# board.net
KiCad netlist of a schematic drawn in EAGLE
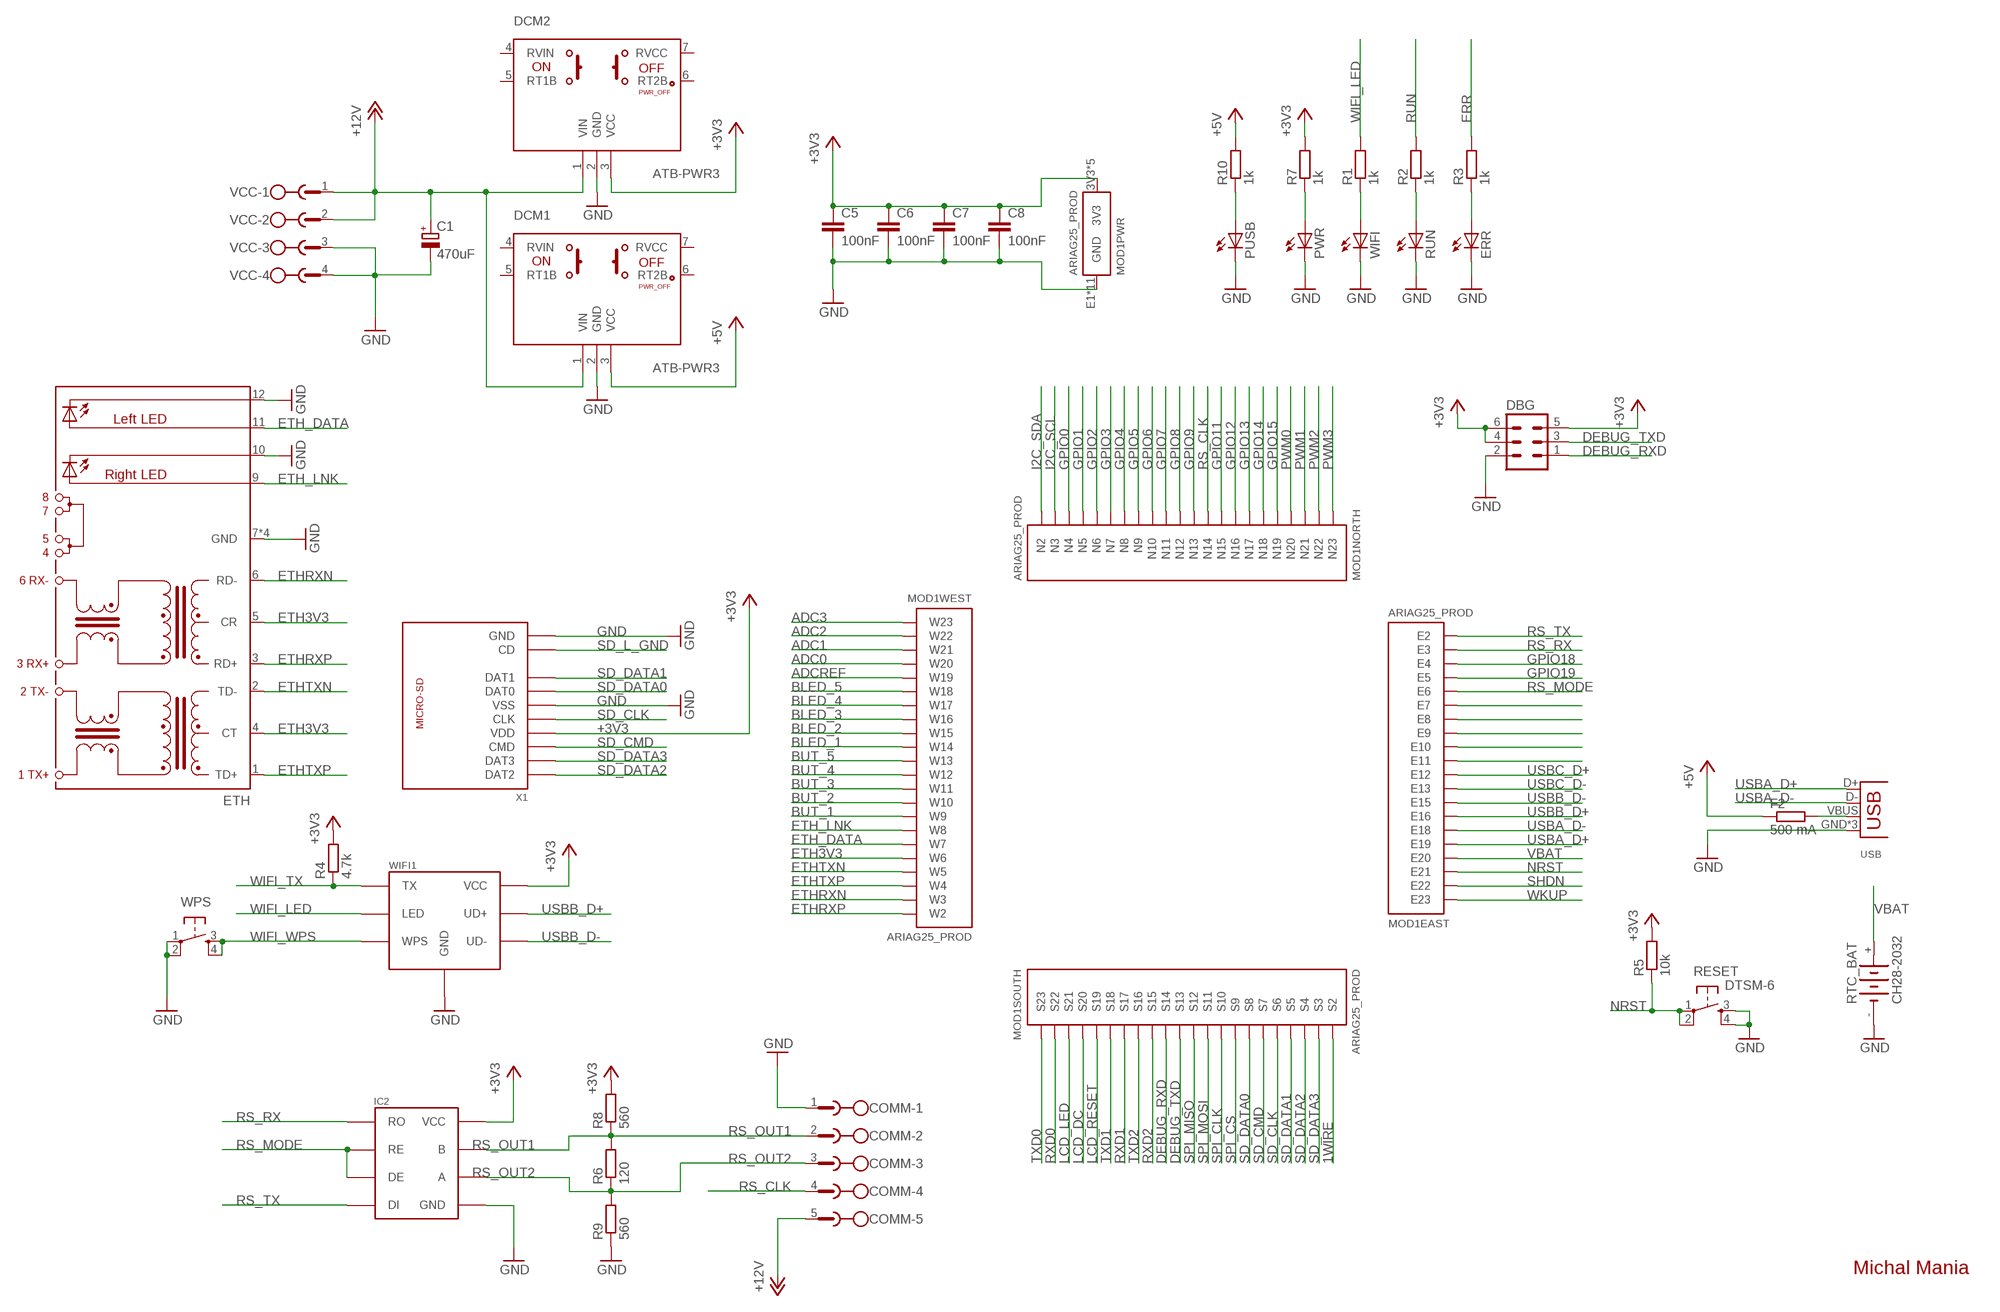
[diagram p0: schematic, sheet 1]

(export (version "E")
  (design (tool "Eeschema 10.0.6"))
  (components
    (comp (ref "C1")
      (value "470uF")
      (footprint "eagle-import:PANASONIC_G")
      (libsource (lib "eagle-import") (part "CPOL-EUG"))
    )
    (comp (ref "C5")
      (value "100nF")
      (footprint "eagle-import:C0805")
      (libsource (lib "eagle-import") (part "C-EUC0805"))
    )
    (comp (ref "C6")
      (value "100nF")
      (footprint "eagle-import:C0805")
      (libsource (lib "eagle-import") (part "C-EUC0805"))
    )
    (comp (ref "C7")
      (value "100nF")
      (footprint "eagle-import:C0805")
      (libsource (lib "eagle-import") (part "C-EUC0805"))
    )
    (comp (ref "C8")
      (value "100nF")
      (footprint "eagle-import:C0805")
      (libsource (lib "eagle-import") (part "C-EUC0805"))
    )
    (comp (ref "COMM")
      (value "MSTBV5")
      (footprint "eagle-import:MSTBV5")
      (fields (field (name "MPN") "MSTBV 2,5/5-GF-5.08"))
      (libsource (lib "eagle-import") (part "MSTBV5"))
    )
    (comp (ref "DBG")
      (value "MA03-2")
      (footprint "eagle-import:MA03-2")
      (fields (field (name "OC_FARNELL") "unknown") (field (name "OC_NEWARK") "unknown"))
      (libsource (lib "eagle-import") (part "MA03-2"))
    )
    (comp (ref "DCM1")
      (value "ATB-PWR3")
      (footprint "eagle-import:ATB-PWR3")
      (libsource (lib "eagle-import") (part "ATB-PWR3"))
    )
    (comp (ref "DCM2")
      (value "ATB-PWR3")
      (footprint "eagle-import:ATB-PWR3")
      (libsource (lib "eagle-import") (part "ATB-PWR3"))
    )
    (comp (ref "ERR")
      (value "LEDSML0805")
      (footprint "eagle-import:SML0805")
      (libsource (lib "eagle-import") (part "LEDSML0805"))
    )
    (comp (ref "ETH")
      (value "J21388")
      (footprint "eagle-import:J1_3_TOP")
      (libsource (lib "eagle-import") (part "J21388"))
    )
    (comp (ref "F2")
      (value "500 mA")
      (footprint "eagle-import:R0805")
      (libsource (lib "eagle-import") (part "R-EU_R0805"))
    )
    (comp (ref "IC2")
      (value "MAX3485")
      (footprint "eagle-import:SO-8")
      (libsource (lib "eagle-import") (part "MAX3485"))
    )
    (comp (ref "MOD1")
      (value "ARIAG25_PROD")
      (footprint "eagle-import:G25_D")
      (libsource (lib "eagle-import") (part "ARIAG25_PROD"))
    )
    (comp (ref "PUSB")
      (value "LEDSML0805")
      (footprint "eagle-import:SML0805")
      (libsource (lib "eagle-import") (part "LEDSML0805"))
    )
    (comp (ref "PWR")
      (value "LEDSML0805")
      (footprint "eagle-import:SML0805")
      (libsource (lib "eagle-import") (part "LEDSML0805"))
    )
    (comp (ref "R1")
      (value "1k")
      (footprint "eagle-import:R0805")
      (libsource (lib "eagle-import") (part "R-EU_R0805"))
    )
    (comp (ref "R2")
      (value "1k")
      (footprint "eagle-import:R0805")
      (libsource (lib "eagle-import") (part "R-EU_R0805"))
    )
    (comp (ref "R3")
      (value "1k")
      (footprint "eagle-import:R0805")
      (libsource (lib "eagle-import") (part "R-EU_R0805"))
    )
    (comp (ref "R4")
      (value "4.7k")
      (footprint "eagle-import:R0805")
      (libsource (lib "eagle-import") (part "R-EU_R0805"))
    )
    (comp (ref "R5")
      (value "10k")
      (footprint "eagle-import:R0805")
      (libsource (lib "eagle-import") (part "R-EU_R0805"))
    )
    (comp (ref "R6")
      (value "120")
      (footprint "eagle-import:R0805")
      (libsource (lib "eagle-import") (part "R-EU_R0805"))
    )
    (comp (ref "R7")
      (value "1k")
      (footprint "eagle-import:R0805")
      (libsource (lib "eagle-import") (part "R-EU_R0805"))
    )
    (comp (ref "R8")
      (value "560")
      (footprint "eagle-import:R0805")
      (libsource (lib "eagle-import") (part "R-EU_R0805"))
    )
    (comp (ref "R9")
      (value "560")
      (footprint "eagle-import:R0805")
      (libsource (lib "eagle-import") (part "R-EU_R0805"))
    )
    (comp (ref "R10")
      (value "1k")
      (footprint "eagle-import:R0805")
      (libsource (lib "eagle-import") (part "R-EU_R0805"))
    )
    (comp (ref "RESET")
      (value "DTSM-6")
      (footprint "eagle-import:DTSM-6")
      (libsource (lib "eagle-import") (part "DTSM-6"))
    )
    (comp (ref "RTC_BAT")
      (value "CH28-2032")
      (footprint "eagle-import:CH28-2032")
      (libsource (lib "eagle-import") (part "CH28-2032"))
    )
    (comp (ref "RUN")
      (value "LEDSML0805")
      (footprint "eagle-import:SML0805")
      (libsource (lib "eagle-import") (part "LEDSML0805"))
    )
    (comp (ref "USB")
      (value "USBA-P")
      (footprint "eagle-import:USB-A-P")
      (libsource (lib "eagle-import") (part "USBA-P"))
    )
    (comp (ref "VCC")
      (value "MSTBV4")
      (footprint "eagle-import:MSTBV4")
      (fields (field (name "MPN") "MSTBV 2,5/4-GF-5.08"))
      (libsource (lib "eagle-import") (part "MSTBV4"))
    )
    (comp (ref "WIFI")
      (value "LEDSML0805")
      (footprint "eagle-import:SML0805")
      (libsource (lib "eagle-import") (part "LEDSML0805"))
    )
    (comp (ref "WIFI1")
      (value "WIFI-2-OEM")
      (footprint "eagle-import:WIFI")
      (libsource (lib "eagle-import") (part "WIFI-2-OEM"))
    )
    (comp (ref "WPS")
      (value "DTSM-6")
      (footprint "eagle-import:DTSM-6")
      (libsource (lib "eagle-import") (part "DTSM-6"))
    )
    (comp (ref "X1")
      (value "MICRO-SD")
      (footprint "eagle-import:112I-TDAR-R")
      (libsource (lib "eagle-import") (part "MICRO-SD"))
    )
  )
  (nets
    (net (code "1") (name "+3V3") (class "Default")
      (node (ref "C5") (pin "1") (pinfunction "1_1") (pintype "passive"))
      (node (ref "C6") (pin "1") (pinfunction "1_1") (pintype "passive"))
      (node (ref "C7") (pin "1") (pinfunction "1_1") (pintype "passive"))
      (node (ref "C8") (pin "1") (pinfunction "1_1") (pintype "passive"))
      (node (ref "DBG") (pin "4") (pinfunction "4_4") (pintype "passive"))
      (node (ref "DBG") (pin "5") (pinfunction "5_5") (pintype "passive"))
      (node (ref "DBG") (pin "6") (pinfunction "6_6") (pintype "passive"))
      (node (ref "DCM2") (pin "3") (pinfunction "VCC_3") (pintype "power_in"))
      (node (ref "IC2") (pin "VCC") (pinfunction "VCC_VCC") (pintype "bidirectional"))
      (node (ref "MOD1") (pin "3V3") (pinfunction "3V3_3V3") (pintype "power_in"))
      (node (ref "MOD1") (pin "E24") (pinfunction "3V3_E24") (pintype "power_in"))
      (node (ref "MOD1") (pin "N1") (pinfunction "3V3_N1") (pintype "power_in"))
      (node (ref "MOD1") (pin "S1") (pinfunction "3V3_S1") (pintype "power_in"))
      (node (ref "MOD1") (pin "W24") (pinfunction "3V3_W24") (pintype "power_in"))
      (node (ref "R4") (pin "2") (pinfunction "2_2") (pintype "passive"))
      (node (ref "R5") (pin "2") (pinfunction "2_2") (pintype "passive"))
      (node (ref "R7") (pin "2") (pinfunction "2_2") (pintype "passive"))
      (node (ref "R8") (pin "2") (pinfunction "2_2") (pintype "passive"))
      (node (ref "WIFI1") (pin "VCC") (pinfunction "VCC_VCC") (pintype "bidirectional"))
      (node (ref "X1") (pin "4") (pinfunction "VDD_4") (pintype "bidirectional"))
    )
    (net (code "2") (name "+5V") (class "Default")
      (node (ref "DCM1") (pin "3") (pinfunction "VCC_3") (pintype "power_in"))
      (node (ref "F2") (pin "1") (pinfunction "1_1") (pintype "passive"))
      (node (ref "R10") (pin "2") (pinfunction "2_2") (pintype "passive"))
    )
    (net (code "3") (name "+12V") (class "Default")
      (node (ref "C1") (pin "+") (pinfunction "+_+") (pintype "passive"))
      (node (ref "COMM") (pin "5") (pinfunction "1_5") (pintype "passive"))
      (node (ref "DCM1") (pin "1") (pinfunction "VIN_1") (pintype "power_in"))
      (node (ref "DCM2") (pin "1") (pinfunction "VIN_1") (pintype "power_in"))
      (node (ref "VCC") (pin "1") (pinfunction "1_1") (pintype "passive"))
      (node (ref "VCC") (pin "2") (pinfunction "1_2") (pintype "passive"))
    )
    (net (code "4") (name "/1WIRE") (class "Default")
      (node (ref "MOD1") (pin "S2") (pinfunction "S2_S2") (pintype "bidirectional"))
    )
    (net (code "5") (name "/ADC0") (class "Default")
      (node (ref "MOD1") (pin "W20") (pinfunction "W20_W20") (pintype "bidirectional"))
    )
    (net (code "6") (name "/ADC1") (class "Default")
      (node (ref "MOD1") (pin "W21") (pinfunction "W21_W21") (pintype "bidirectional"))
    )
    (net (code "7") (name "/ADC2") (class "Default")
      (node (ref "MOD1") (pin "W22") (pinfunction "W22_W22") (pintype "bidirectional"))
    )
    (net (code "8") (name "/ADC3") (class "Default")
      (node (ref "MOD1") (pin "W23") (pinfunction "W23_W23") (pintype "bidirectional"))
    )
    (net (code "9") (name "/ADCREF") (class "Default")
      (node (ref "MOD1") (pin "W19") (pinfunction "W19_W19") (pintype "bidirectional"))
    )
    (net (code "10") (name "/BLED_1") (class "Default")
      (node (ref "MOD1") (pin "W14") (pinfunction "W14_W14") (pintype "bidirectional"))
    )
    (net (code "11") (name "/BLED_2") (class "Default")
      (node (ref "MOD1") (pin "W15") (pinfunction "W15_W15") (pintype "bidirectional"))
    )
    (net (code "12") (name "/BLED_3") (class "Default")
      (node (ref "MOD1") (pin "W16") (pinfunction "W16_W16") (pintype "bidirectional"))
    )
    (net (code "13") (name "/BLED_4") (class "Default")
      (node (ref "MOD1") (pin "W17") (pinfunction "W17_W17") (pintype "bidirectional"))
    )
    (net (code "14") (name "/BLED_5") (class "Default")
      (node (ref "MOD1") (pin "W18") (pinfunction "W18_W18") (pintype "bidirectional"))
    )
    (net (code "15") (name "/BUT_1") (class "Default")
      (node (ref "MOD1") (pin "W9") (pinfunction "W9_W9") (pintype "bidirectional"))
    )
    (net (code "16") (name "/BUT_2") (class "Default")
      (node (ref "MOD1") (pin "W10") (pinfunction "W10_W10") (pintype "bidirectional"))
    )
    (net (code "17") (name "/BUT_3") (class "Default")
      (node (ref "MOD1") (pin "W11") (pinfunction "W11_W11") (pintype "bidirectional"))
    )
    (net (code "18") (name "/BUT_4") (class "Default")
      (node (ref "MOD1") (pin "W12") (pinfunction "W12_W12") (pintype "bidirectional"))
    )
    (net (code "19") (name "/BUT_5") (class "Default")
      (node (ref "MOD1") (pin "W13") (pinfunction "W13_W13") (pintype "bidirectional"))
    )
    (net (code "20") (name "/DEBUG_RXD") (class "Default")
      (node (ref "DBG") (pin "1") (pinfunction "1_1") (pintype "passive"))
      (node (ref "MOD1") (pin "S14") (pinfunction "S14_S14") (pintype "bidirectional"))
    )
    (net (code "21") (name "/DEBUG_TXD") (class "Default")
      (node (ref "DBG") (pin "3") (pinfunction "3_3") (pintype "passive"))
      (node (ref "MOD1") (pin "S13") (pinfunction "S13_S13") (pintype "bidirectional"))
    )
    (net (code "22") (name "/ERR") (class "Default")
      (node (ref "R3") (pin "2") (pinfunction "2_2") (pintype "passive"))
    )
    (net (code "23") (name "/ETH3V3") (class "Default")
      (node (ref "ETH") (pin "4") (pinfunction "CT_4") (pintype "input"))
      (node (ref "ETH") (pin "5") (pinfunction "CR_5") (pintype "input"))
      (node (ref "MOD1") (pin "W6") (pinfunction "W6_W6") (pintype "bidirectional"))
    )
    (net (code "24") (name "/ETHRXN") (class "Default")
      (node (ref "ETH") (pin "6") (pinfunction "RD-_6") (pintype "input"))
      (node (ref "MOD1") (pin "W3") (pinfunction "W3_W3") (pintype "bidirectional"))
    )
    (net (code "25") (name "/ETHRXP") (class "Default")
      (node (ref "ETH") (pin "3") (pinfunction "RD+_3") (pintype "input"))
      (node (ref "MOD1") (pin "W2") (pinfunction "W2_W2") (pintype "bidirectional"))
    )
    (net (code "26") (name "/ETHTXN") (class "Default")
      (node (ref "ETH") (pin "2") (pinfunction "TD-_2") (pintype "input"))
      (node (ref "MOD1") (pin "W5") (pinfunction "W5_W5") (pintype "bidirectional"))
    )
    (net (code "27") (name "/ETHTXP") (class "Default")
      (node (ref "ETH") (pin "1") (pinfunction "TD+_1") (pintype "input"))
      (node (ref "MOD1") (pin "W4") (pinfunction "W4_W4") (pintype "bidirectional"))
    )
    (net (code "28") (name "/ETH_DATA") (class "Default")
      (node (ref "ETH") (pin "11") (pinfunction "L+_11") (pintype "passive"))
      (node (ref "MOD1") (pin "W7") (pinfunction "W7_W7") (pintype "bidirectional"))
    )
    (net (code "29") (name "/ETH_LNK") (class "Default")
      (node (ref "ETH") (pin "9") (pinfunction "R+_9") (pintype "passive"))
      (node (ref "MOD1") (pin "W8") (pinfunction "W8_W8") (pintype "bidirectional"))
    )
    (net (code "30") (name "/GPIO0") (class "Default")
      (node (ref "MOD1") (pin "N4") (pinfunction "N4_N4") (pintype "bidirectional"))
    )
    (net (code "31") (name "/GPIO1") (class "Default")
      (node (ref "MOD1") (pin "N5") (pinfunction "N5_N5") (pintype "bidirectional"))
    )
    (net (code "32") (name "/GPIO2") (class "Default")
      (node (ref "MOD1") (pin "N6") (pinfunction "N6_N6") (pintype "bidirectional"))
    )
    (net (code "33") (name "/GPIO3") (class "Default")
      (node (ref "MOD1") (pin "N7") (pinfunction "N7_N7") (pintype "bidirectional"))
    )
    (net (code "34") (name "/GPIO4") (class "Default")
      (node (ref "MOD1") (pin "N8") (pinfunction "N8_N8") (pintype "bidirectional"))
    )
    (net (code "35") (name "/GPIO5") (class "Default")
      (node (ref "MOD1") (pin "N9") (pinfunction "N9_N9") (pintype "bidirectional"))
    )
    (net (code "36") (name "/GPIO6") (class "Default")
      (node (ref "MOD1") (pin "N10") (pinfunction "N10_N10") (pintype "bidirectional"))
    )
    (net (code "37") (name "/GPIO7") (class "Default")
      (node (ref "MOD1") (pin "N11") (pinfunction "N11_N11") (pintype "bidirectional"))
    )
    (net (code "38") (name "/GPIO8") (class "Default")
      (node (ref "MOD1") (pin "N12") (pinfunction "N12_N12") (pintype "bidirectional"))
    )
    (net (code "39") (name "/GPIO9") (class "Default")
      (node (ref "MOD1") (pin "N13") (pinfunction "N13_N13") (pintype "bidirectional"))
    )
    (net (code "40") (name "/GPIO11") (class "Default")
      (node (ref "MOD1") (pin "N15") (pinfunction "N15_N15") (pintype "bidirectional"))
    )
    (net (code "41") (name "/GPIO12") (class "Default")
      (node (ref "MOD1") (pin "N16") (pinfunction "N16_N16") (pintype "bidirectional"))
    )
    (net (code "42") (name "/GPIO13") (class "Default")
      (node (ref "MOD1") (pin "N17") (pinfunction "N17_N17") (pintype "bidirectional"))
    )
    (net (code "43") (name "/GPIO14") (class "Default")
      (node (ref "MOD1") (pin "N18") (pinfunction "N18_N18") (pintype "bidirectional"))
    )
    (net (code "44") (name "/GPIO15") (class "Default")
      (node (ref "MOD1") (pin "N19") (pinfunction "N19_N19") (pintype "bidirectional"))
    )
    (net (code "45") (name "/GPIO18") (class "Default")
      (node (ref "MOD1") (pin "E4") (pinfunction "E4_E4") (pintype "bidirectional"))
    )
    (net (code "46") (name "/GPIO19") (class "Default")
      (node (ref "MOD1") (pin "E5") (pinfunction "E5_E5") (pintype "bidirectional"))
    )
    (net (code "47") (name "/I2C_SCL") (class "Default")
      (node (ref "MOD1") (pin "N3") (pinfunction "N3_N3") (pintype "bidirectional"))
    )
    (net (code "48") (name "/I2C_SDA") (class "Default")
      (node (ref "MOD1") (pin "N2") (pinfunction "N2_N2") (pintype "bidirectional"))
    )
    (net (code "49") (name "/LCD_DC") (class "Default")
      (node (ref "MOD1") (pin "S20") (pinfunction "S20_S20") (pintype "bidirectional"))
    )
    (net (code "50") (name "/LCD_LED") (class "Default")
      (node (ref "MOD1") (pin "S21") (pinfunction "S21_S21") (pintype "bidirectional"))
    )
    (net (code "51") (name "/LCD_RESET") (class "Default")
      (node (ref "MOD1") (pin "S19") (pinfunction "S19_S19") (pintype "bidirectional"))
    )
    (net (code "52") (name "/NRST") (class "Default")
      (node (ref "MOD1") (pin "E21") (pinfunction "E21_E21") (pintype "bidirectional"))
      (node (ref "R5") (pin "1") (pinfunction "1_1") (pintype "passive"))
      (node (ref "RESET") (pin "1") (pinfunction "1_1") (pintype "passive"))
      (node (ref "RESET") (pin "2") (pinfunction "2_2") (pintype "passive"))
    )
    (net (code "53") (name "/PWM0") (class "Default")
      (node (ref "MOD1") (pin "N20") (pinfunction "N20_N20") (pintype "bidirectional"))
    )
    (net (code "54") (name "/PWM1") (class "Default")
      (node (ref "MOD1") (pin "N21") (pinfunction "N21_N21") (pintype "bidirectional"))
    )
    (net (code "55") (name "/PWM2") (class "Default")
      (node (ref "MOD1") (pin "N22") (pinfunction "N22_N22") (pintype "bidirectional"))
    )
    (net (code "56") (name "/PWM3") (class "Default")
      (node (ref "MOD1") (pin "N23") (pinfunction "N23_N23") (pintype "bidirectional"))
    )
    (net (code "57") (name "/RS_CLK") (class "Default")
      (node (ref "COMM") (pin "4") (pinfunction "1_4") (pintype "passive"))
      (node (ref "MOD1") (pin "N14") (pinfunction "N14_N14") (pintype "bidirectional"))
    )
    (net (code "58") (name "/RS_MODE") (class "Default")
      (node (ref "IC2") (pin "DE") (pinfunction "DE_DE") (pintype "bidirectional"))
      (node (ref "IC2") (pin "RE") (pinfunction "RE_RE") (pintype "bidirectional"))
      (node (ref "MOD1") (pin "E6") (pinfunction "E6_E6") (pintype "bidirectional"))
    )
    (net (code "59") (name "/RS_OUT1") (class "Default")
      (node (ref "COMM") (pin "2") (pinfunction "1_2") (pintype "passive"))
      (node (ref "IC2") (pin "B") (pinfunction "B_B") (pintype "bidirectional"))
      (node (ref "R6") (pin "2") (pinfunction "2_2") (pintype "passive"))
      (node (ref "R8") (pin "1") (pinfunction "1_1") (pintype "passive"))
    )
    (net (code "60") (name "/RS_OUT2") (class "Default")
      (node (ref "COMM") (pin "3") (pinfunction "1_3") (pintype "passive"))
      (node (ref "IC2") (pin "A") (pinfunction "A_A") (pintype "bidirectional"))
      (node (ref "R6") (pin "1") (pinfunction "1_1") (pintype "passive"))
      (node (ref "R9") (pin "2") (pinfunction "2_2") (pintype "passive"))
    )
    (net (code "61") (name "/RS_RX") (class "Default")
      (node (ref "IC2") (pin "RO") (pinfunction "RO_RO") (pintype "bidirectional"))
      (node (ref "MOD1") (pin "E3") (pinfunction "E3_E3") (pintype "bidirectional"))
    )
    (net (code "62") (name "/RS_TX") (class "Default")
      (node (ref "IC2") (pin "DI") (pinfunction "DI_DI") (pintype "bidirectional"))
      (node (ref "MOD1") (pin "E2") (pinfunction "E2_E2") (pintype "bidirectional"))
    )
    (net (code "63") (name "/RUN") (class "Default")
      (node (ref "R2") (pin "2") (pinfunction "2_2") (pintype "passive"))
    )
    (net (code "64") (name "/RXD0") (class "Default")
      (node (ref "MOD1") (pin "S22") (pinfunction "S22_S22") (pintype "bidirectional"))
    )
    (net (code "65") (name "/RXD1") (class "Default")
      (node (ref "MOD1") (pin "S17") (pinfunction "S17_S17") (pintype "bidirectional"))
    )
    (net (code "66") (name "/RXD2") (class "Default")
      (node (ref "MOD1") (pin "S15") (pinfunction "S15_S15") (pintype "bidirectional"))
    )
    (net (code "67") (name "/SD_CLK") (class "Default")
      (node (ref "MOD1") (pin "S6") (pinfunction "S6_S6") (pintype "bidirectional"))
      (node (ref "X1") (pin "5") (pinfunction "CLK_5") (pintype "bidirectional"))
    )
    (net (code "68") (name "/SD_CMD") (class "Default")
      (node (ref "MOD1") (pin "S7") (pinfunction "S7_S7") (pintype "bidirectional"))
      (node (ref "X1") (pin "3") (pinfunction "CMD_3") (pintype "bidirectional"))
    )
    (net (code "69") (name "/SD_DATA0") (class "Default")
      (node (ref "MOD1") (pin "S8") (pinfunction "S8_S8") (pintype "bidirectional"))
      (node (ref "X1") (pin "7") (pinfunction "DAT0_7") (pintype "bidirectional"))
    )
    (net (code "70") (name "/SD_DATA1") (class "Default")
      (node (ref "MOD1") (pin "S5") (pinfunction "S5_S5") (pintype "bidirectional"))
      (node (ref "X1") (pin "8") (pinfunction "DAT1_8") (pintype "bidirectional"))
    )
    (net (code "71") (name "/SD_DATA2") (class "Default")
      (node (ref "MOD1") (pin "S4") (pinfunction "S4_S4") (pintype "bidirectional"))
      (node (ref "X1") (pin "1") (pinfunction "DAT2_1") (pintype "bidirectional"))
    )
    (net (code "72") (name "/SD_DATA3") (class "Default")
      (node (ref "MOD1") (pin "S3") (pinfunction "S3_S3") (pintype "bidirectional"))
      (node (ref "X1") (pin "2") (pinfunction "DAT3_2") (pintype "bidirectional"))
    )
    (net (code "73") (name "/SD_L_GND") (class "Default")
      (node (ref "X1") (pin "CD") (pinfunction "CD_CD") (pintype "bidirectional"))
    )
    (net (code "74") (name "/SHDN") (class "Default")
      (node (ref "MOD1") (pin "E22") (pinfunction "E22_E22") (pintype "bidirectional"))
    )
    (net (code "75") (name "/SPI_CLK") (class "Default")
      (node (ref "MOD1") (pin "S10") (pinfunction "S10_S10") (pintype "bidirectional"))
    )
    (net (code "76") (name "/SPI_CS") (class "Default")
      (node (ref "MOD1") (pin "S9") (pinfunction "S9_S9") (pintype "bidirectional"))
    )
    (net (code "77") (name "/SPI_MISO") (class "Default")
      (node (ref "MOD1") (pin "S12") (pinfunction "S12_S12") (pintype "bidirectional"))
    )
    (net (code "78") (name "/SPI_MOSI") (class "Default")
      (node (ref "MOD1") (pin "S11") (pinfunction "S11_S11") (pintype "bidirectional"))
    )
    (net (code "79") (name "/TXD0") (class "Default")
      (node (ref "MOD1") (pin "S23") (pinfunction "S23_S23") (pintype "bidirectional"))
    )
    (net (code "80") (name "/TXD1") (class "Default")
      (node (ref "MOD1") (pin "S18") (pinfunction "S18_S18") (pintype "bidirectional"))
    )
    (net (code "81") (name "/TXD2") (class "Default")
      (node (ref "MOD1") (pin "S16") (pinfunction "S16_S16") (pintype "bidirectional"))
    )
    (net (code "82") (name "/USBA_D+") (class "Default")
      (node (ref "MOD1") (pin "E19") (pinfunction "E19_E19") (pintype "bidirectional"))
      (node (ref "USB") (pin "D+") (pinfunction "D+_D+") (pintype "bidirectional"))
    )
    (net (code "83") (name "/USBA_D-") (class "Default")
      (node (ref "MOD1") (pin "E18") (pinfunction "E18_E18") (pintype "bidirectional"))
      (node (ref "USB") (pin "D-") (pinfunction "D-_D-") (pintype "bidirectional"))
    )
    (net (code "84") (name "/USBB_D+") (class "Default")
      (node (ref "MOD1") (pin "E16") (pinfunction "E16_E16") (pintype "bidirectional"))
      (node (ref "WIFI1") (pin "UD+") (pinfunction "UD+_UD+") (pintype "bidirectional"))
    )
    (net (code "85") (name "/USBB_D-") (class "Default")
      (node (ref "MOD1") (pin "E15") (pinfunction "E15_E15") (pintype "bidirectional"))
      (node (ref "WIFI1") (pin "UD-") (pinfunction "UD-_UD-") (pintype "bidirectional"))
    )
    (net (code "86") (name "/USBC_D+") (class "Default")
      (node (ref "MOD1") (pin "E12") (pinfunction "E12_E12") (pintype "bidirectional"))
    )
    (net (code "87") (name "/USBC_D-") (class "Default")
      (node (ref "MOD1") (pin "E13") (pinfunction "E13_E13") (pintype "bidirectional"))
    )
    (net (code "88") (name "/VBAT") (class "Default")
      (node (ref "MOD1") (pin "E20") (pinfunction "E20_E20") (pintype "bidirectional"))
      (node (ref "RTC_BAT") (pin "+") (pinfunction "+_+") (pintype "passive"))
    )
    (net (code "89") (name "/WIFI_LED") (class "Default")
      (node (ref "R1") (pin "2") (pinfunction "2_2") (pintype "passive"))
      (node (ref "WIFI1") (pin "LED") (pinfunction "LED_LED") (pintype "bidirectional"))
    )
    (net (code "90") (name "/WIFI_TX") (class "Default")
      (node (ref "R4") (pin "1") (pinfunction "1_1") (pintype "passive"))
      (node (ref "WIFI1") (pin "TX") (pinfunction "TX_TX") (pintype "bidirectional"))
    )
    (net (code "91") (name "/WIFI_WPS") (class "Default")
      (node (ref "WIFI1") (pin "WPS") (pinfunction "WPS_WPS") (pintype "bidirectional"))
      (node (ref "WPS") (pin "3") (pinfunction "3_3") (pintype "passive"))
      (node (ref "WPS") (pin "4") (pinfunction "4_4") (pintype "passive"))
    )
    (net (code "92") (name "/WKUP") (class "Default")
      (node (ref "MOD1") (pin "E23") (pinfunction "E23_E23") (pintype "bidirectional"))
    )
    (net (code "93") (name "GND") (class "Default")
      (node (ref "C1") (pin "-") (pinfunction "-_-") (pintype "passive"))
      (node (ref "C5") (pin "2") (pinfunction "2_2") (pintype "passive"))
      (node (ref "C6") (pin "2") (pinfunction "2_2") (pintype "passive"))
      (node (ref "C7") (pin "2") (pinfunction "2_2") (pintype "passive"))
      (node (ref "C8") (pin "2") (pinfunction "2_2") (pintype "passive"))
      (node (ref "COMM") (pin "1") (pinfunction "1_1") (pintype "passive"))
      (node (ref "DBG") (pin "2") (pinfunction "2_2") (pintype "passive"))
      (node (ref "DCM1") (pin "2") (pinfunction "GND_2") (pintype "power_in"))
      (node (ref "DCM2") (pin "2") (pinfunction "GND_2") (pintype "power_in"))
      (node (ref "ERR") (pin "C") (pinfunction "C_C") (pintype "passive"))
      (node (ref "ETH") (pin "10") (pinfunction "R-_10") (pintype "passive"))
      (node (ref "ETH") (pin "12") (pinfunction "L-_12") (pintype "passive"))
      (node (ref "ETH") (pin "7") (pinfunction "GND_7") (pintype "input"))
      (node (ref "ETH") (pin "8") (pinfunction "GND_8") (pintype "input"))
      (node (ref "ETH") (pin "M1") (pinfunction "GND_M1") (pintype "input"))
      (node (ref "ETH") (pin "M2") (pinfunction "GND_M2") (pintype "input"))
      (node (ref "IC2") (pin "GND") (pinfunction "GND_GND") (pintype "bidirectional"))
      (node (ref "MOD1") (pin "E1") (pinfunction "GND_E1") (pintype "power_in"))
      (node (ref "MOD1") (pin "E14") (pinfunction "GND_E14") (pintype "power_in"))
      (node (ref "MOD1") (pin "E17") (pinfunction "GND_E17") (pintype "power_in"))
      (node (ref "MOD1") (pin "GND@1") (pinfunction "GND_GND@1") (pintype "power_in"))
      (node (ref "MOD1") (pin "GND@2") (pinfunction "GND_GND@2") (pintype "power_in"))
      (node (ref "MOD1") (pin "GND@3") (pinfunction "GND_GND@3") (pintype "power_in"))
      (node (ref "MOD1") (pin "GND@4") (pinfunction "GND_GND@4") (pintype "power_in"))
      (node (ref "MOD1") (pin "GND@5") (pinfunction "GND_GND@5") (pintype "power_in"))
      (node (ref "MOD1") (pin "N24") (pinfunction "GND_N24") (pintype "power_in"))
      (node (ref "MOD1") (pin "S24") (pinfunction "GND_S24") (pintype "power_in"))
      (node (ref "MOD1") (pin "W1") (pinfunction "GND_W1") (pintype "power_in"))
      (node (ref "PUSB") (pin "C") (pinfunction "C_C") (pintype "passive"))
      (node (ref "PWR") (pin "C") (pinfunction "C_C") (pintype "passive"))
      (node (ref "R9") (pin "1") (pinfunction "1_1") (pintype "passive"))
      (node (ref "RESET") (pin "3") (pinfunction "3_3") (pintype "passive"))
      (node (ref "RESET") (pin "4") (pinfunction "4_4") (pintype "passive"))
      (node (ref "RTC_BAT") (pin "-") (pinfunction "-_-") (pintype "passive"))
      (node (ref "RUN") (pin "C") (pinfunction "C_C") (pintype "passive"))
      (node (ref "USB") (pin "GND") (pinfunction "GND_GND") (pintype "bidirectional"))
      (node (ref "USB") (pin "P$5") (pinfunction "GND_P$5") (pintype "bidirectional"))
      (node (ref "USB") (pin "P$6") (pinfunction "GND_P$6") (pintype "bidirectional"))
      (node (ref "VCC") (pin "3") (pinfunction "1_3") (pintype "passive"))
      (node (ref "VCC") (pin "4") (pinfunction "1_4") (pintype "passive"))
      (node (ref "WIFI") (pin "C") (pinfunction "C_C") (pintype "passive"))
      (node (ref "WIFI1") (pin "GND") (pinfunction "GND_GND") (pintype "bidirectional"))
      (node (ref "WPS") (pin "1") (pinfunction "1_1") (pintype "passive"))
      (node (ref "WPS") (pin "2") (pinfunction "2_2") (pintype "passive"))
      (node (ref "X1") (pin "6") (pinfunction "VSS_6") (pintype "bidirectional"))
      (node (ref "X1") (pin "GND_A") (pinfunction "GND_GND_A") (pintype "bidirectional"))
      (node (ref "X1") (pin "GND_B") (pinfunction "GND_GND_B") (pintype "bidirectional"))
      (node (ref "X1") (pin "GND_C") (pinfunction "GND_GND_C") (pintype "bidirectional"))
    )
    (net (code "94") (name "Net-(ERR-PadA)") (class "Default")
      (node (ref "ERR") (pin "A") (pinfunction "A_A") (pintype "passive"))
      (node (ref "R3") (pin "1") (pinfunction "1_1") (pintype "passive"))
    )
    (net (code "95") (name "Net-(F2-Pad2)") (class "Default")
      (node (ref "F2") (pin "2") (pinfunction "2_2") (pintype "passive"))
      (node (ref "USB") (pin "VBUS") (pinfunction "VBUS_VBUS") (pintype "bidirectional"))
    )
    (net (code "96") (name "Net-(PUSB-PadA)") (class "Default")
      (node (ref "PUSB") (pin "A") (pinfunction "A_A") (pintype "passive"))
      (node (ref "R10") (pin "1") (pinfunction "1_1") (pintype "passive"))
    )
    (net (code "97") (name "Net-(PWR-PadA)") (class "Default")
      (node (ref "PWR") (pin "A") (pinfunction "A_A") (pintype "passive"))
      (node (ref "R7") (pin "1") (pinfunction "1_1") (pintype "passive"))
    )
    (net (code "98") (name "Net-(R1-Pad1)") (class "Default")
      (node (ref "R1") (pin "1") (pinfunction "1_1") (pintype "passive"))
      (node (ref "WIFI") (pin "A") (pinfunction "A_A") (pintype "passive"))
    )
    (net (code "99") (name "Net-(R2-Pad1)") (class "Default")
      (node (ref "R2") (pin "1") (pinfunction "1_1") (pintype "passive"))
      (node (ref "RUN") (pin "A") (pinfunction "A_A") (pintype "passive"))
    )
    (net (code "100") (name "unconnected-(DCM1-RT1B-Pad5)") (class "Default")
      (node (ref "DCM1") (pin "5") (pinfunction "RT1B_5") (pintype "input"))
    )
    (net (code "101") (name "unconnected-(DCM1-RT2B-Pad6)") (class "Default")
      (node (ref "DCM1") (pin "6") (pinfunction "RT2B_6") (pintype "input"))
    )
    (net (code "102") (name "unconnected-(DCM1-RVCC-Pad7)") (class "Default")
      (node (ref "DCM1") (pin "7") (pinfunction "RVCC_7") (pintype "input"))
    )
    (net (code "103") (name "unconnected-(DCM1-RVIN-Pad4)") (class "Default")
      (node (ref "DCM1") (pin "4") (pinfunction "RVIN_4") (pintype "input"))
    )
    (net (code "104") (name "unconnected-(DCM2-RT1B-Pad5)") (class "Default")
      (node (ref "DCM2") (pin "5") (pinfunction "RT1B_5") (pintype "input"))
    )
    (net (code "105") (name "unconnected-(DCM2-RT2B-Pad6)") (class "Default")
      (node (ref "DCM2") (pin "6") (pinfunction "RT2B_6") (pintype "input"))
    )
    (net (code "106") (name "unconnected-(DCM2-RVCC-Pad7)") (class "Default")
      (node (ref "DCM2") (pin "7") (pinfunction "RVCC_7") (pintype "input"))
    )
    (net (code "107") (name "unconnected-(DCM2-RVIN-Pad4)") (class "Default")
      (node (ref "DCM2") (pin "4") (pinfunction "RVIN_4") (pintype "input"))
    )
    (net (code "108") (name "unconnected-(MOD1-PadE7)") (class "Default")
      (node (ref "MOD1") (pin "E7") (pinfunction "E7_E7") (pintype "bidirectional"))
    )
    (net (code "109") (name "unconnected-(MOD1-PadE8)") (class "Default")
      (node (ref "MOD1") (pin "E8") (pinfunction "E8_E8") (pintype "bidirectional"))
    )
    (net (code "110") (name "unconnected-(MOD1-PadE9)") (class "Default")
      (node (ref "MOD1") (pin "E9") (pinfunction "E9_E9") (pintype "bidirectional"))
    )
    (net (code "111") (name "unconnected-(MOD1-PadE10)") (class "Default")
      (node (ref "MOD1") (pin "E10") (pinfunction "E10_E10") (pintype "bidirectional"))
    )
    (net (code "112") (name "unconnected-(MOD1-PadE11)") (class "Default")
      (node (ref "MOD1") (pin "E11") (pinfunction "E11_E11") (pintype "bidirectional"))
    )
  )
)
